# imu_spi.net
KiCad netlist of a schematic drawn in EAGLE
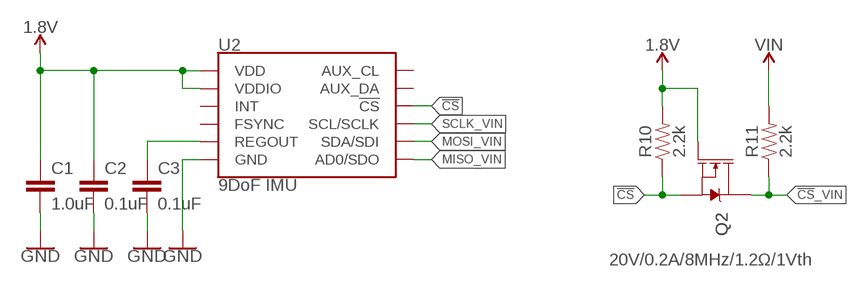
[diagram p0: schematic, sheet 1]

(export (version "E")
  (design (tool "Eeschema 10.0.6"))
  (components
    (comp (ref "C1")
      (value "1.0uF")
      (footprint "eagle-import:0603")
      (libsource (lib "eagle-import") (part "1.0UF-0603-16V-10%-X7R"))
    )
    (comp (ref "C2")
      (value "0.1uF")
      (footprint "eagle-import:0603")
      (libsource (lib "eagle-import") (part "0.1UF-0603-25V-5%"))
    )
    (comp (ref "C3")
      (value "0.1uF")
      (footprint "eagle-import:0603")
      (libsource (lib "eagle-import") (part "0.1UF-0603-25V-5%"))
    )
    (comp (ref "Q2")
      (value "20V/0.2A/8MHz/1.2Ω/1Vth")
      (footprint "eagle-import:SOT-416FL")
      (libsource (lib "eagle-import") (part "MOSFET-NCH-RE1C002UN"))
    )
    (comp (ref "R10")
      (value "2.2k")
      (footprint "eagle-import:0402-TIGHT")
      (libsource (lib "eagle-import") (part "2.2KOHM-0402T-1/16W-1%"))
    )
    (comp (ref "R11")
      (value "2.2k")
      (footprint "eagle-import:0402-TIGHT")
      (libsource (lib "eagle-import") (part "2.2KOHM-0402T-1/16W-1%"))
    )
    (comp (ref "U2")
      (value "9DoF IMU")
      (footprint "eagle-import:QFN24-3X3")
      (libsource (lib "eagle-import") (part "ICM-20948"))
    )
  )
  (nets
    (net (code "1") (name "/~{CS}") (class "Default")
      (node (ref "Q2") (pin "2") (pinfunction "S_2") (pintype "bidirectional"))
      (node (ref "R10") (pin "1") (pinfunction "1_1") (pintype "passive"))
      (node (ref "U2") (pin "22") (pinfunction "~{CS}_22") (pintype "bidirectional"))
    )
    (net (code "2") (name "/~{CS}_VIN") (class "Default")
      (node (ref "Q2") (pin "3") (pinfunction "D_3") (pintype "bidirectional"))
      (node (ref "R11") (pin "1") (pinfunction "1_1") (pintype "passive"))
    )
    (net (code "3") (name "1.8V") (class "Default")
      (node (ref "C1") (pin "1") (pinfunction "1_1") (pintype "passive"))
      (node (ref "C2") (pin "1") (pinfunction "1_1") (pintype "passive"))
      (node (ref "Q2") (pin "1") (pinfunction "G_1") (pintype "bidirectional"))
      (node (ref "R10") (pin "2") (pinfunction "2_2") (pintype "passive"))
      (node (ref "U2") (pin "13") (pinfunction "VDD_13") (pintype "bidirectional"))
      (node (ref "U2") (pin "8") (pinfunction "VDDIO_8") (pintype "bidirectional"))
    )
    (net (code "4") (name "GND") (class "Default")
      (node (ref "C1") (pin "2") (pinfunction "2_2") (pintype "passive"))
      (node (ref "C2") (pin "2") (pinfunction "2_2") (pintype "passive"))
      (node (ref "C3") (pin "2") (pinfunction "2_2") (pintype "passive"))
      (node (ref "U2") (pin "18") (pinfunction "GND_18") (pintype "bidirectional"))
      (node (ref "U2") (pin "20") (pinfunction "GND_20") (pintype "bidirectional"))
    )
    (net (code "5") (name "MISO_VIN") (class "Default")
      (node (ref "U2") (pin "9") (pinfunction "AD0/SDO_9") (pintype "bidirectional"))
    )
    (net (code "6") (name "MOSI_VIN") (class "Default")
      (node (ref "U2") (pin "24") (pinfunction "SDA/SDI_24") (pintype "bidirectional"))
    )
    (net (code "7") (name "Net-(U2-REGOUT)") (class "Default")
      (node (ref "C3") (pin "1") (pinfunction "1_1") (pintype "passive"))
      (node (ref "U2") (pin "10") (pinfunction "REGOUT_10") (pintype "bidirectional"))
    )
    (net (code "8") (name "SCLK_VIN") (class "Default")
      (node (ref "U2") (pin "23") (pinfunction "SCL/SCLK_23") (pintype "bidirectional"))
    )
    (net (code "9") (name "VIN") (class "Default")
      (node (ref "R11") (pin "2") (pinfunction "2_2") (pintype "passive"))
    )
    (net (code "10") (name "unconnected-(U2-AUX_CL-Pad7)") (class "Default")
      (node (ref "U2") (pin "7") (pinfunction "AUX_CL_7") (pintype "bidirectional"))
    )
    (net (code "11") (name "unconnected-(U2-AUX_DA-Pad21)") (class "Default")
      (node (ref "U2") (pin "21") (pinfunction "AUX_DA_21") (pintype "bidirectional"))
    )
    (net (code "12") (name "unconnected-(U2-FSYNC-Pad11)") (class "Default")
      (node (ref "U2") (pin "11") (pinfunction "FSYNC_11") (pintype "bidirectional"))
    )
    (net (code "13") (name "unconnected-(U2-INT-Pad12)") (class "Default")
      (node (ref "U2") (pin "12") (pinfunction "INT_12") (pintype "bidirectional"))
    )
  )
)
